# Motor_Drivers.net
KiCad netlist of a schematic drawn in Altium Designer
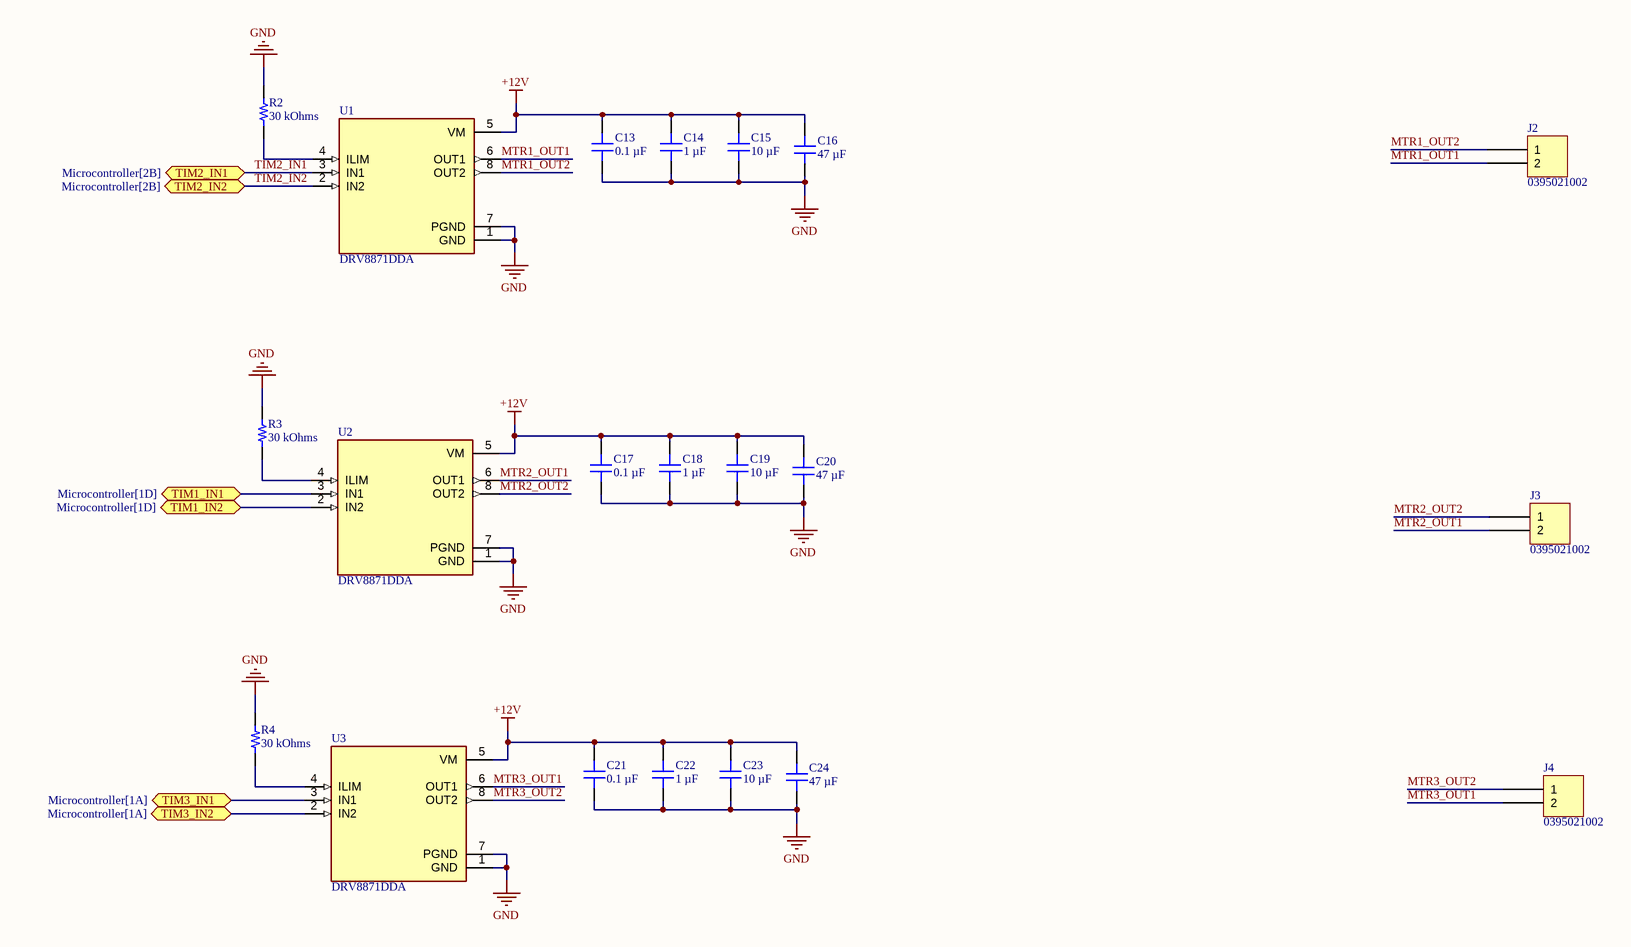
[diagram p0: Motor_Drivers.SchDoc]

(export (version "E")
  (design (tool "Eeschema 10.0.6"))
  (components
    (comp (ref "C13")
      (value "0.1 µF")
      (footprint "CAP 0603_1608")
      (description "CAP CER 0.1UF 25V X7R 0603")
      (fields
        (field (name "PART NUMBER") "C0603X104M3RAC7867")
        (field (name "CAPACITANCE") "0.1 µF")
        (field (name "MANUFACTURER") "KEMET")
      )
      (libsource (lib "Celestial Altium Library - altium_library") (part "Capacitor"))
    )
    (comp (ref "C14")
      (value "1 µF")
      (footprint "MURATA GCM188 0603_1608")
      (description "CAP CER 1UF 16V X7R 0603")
      (fields
        (field (name "PART NUMBER") "GCM188R71C105KA64J")
        (field (name "CAPACITANCE") "1 µF")
        (field (name "MANUFACTURER") "Murata Electronics")
      )
      (libsource (lib "Celestial Altium Library - altium_library") (part "Capacitor"))
    )
    (comp (ref "C15")
      (value "10 µF")
      (footprint "CAP 0603_1608")
      (description "CAP CER 10UF 16V X5R 0603")
      (fields
        (field (name "PART NUMBER") "CC0603MRX5R7BB106")
        (field (name "CAPACITANCE") "10 µF")
        (field (name "MANUFACTURER") "Yageo")
      )
      (libsource (lib "Celestial Altium Library - altium_library") (part "Capacitor"))
    )
    (comp (ref "C16")
      (value "47 µF")
      (footprint "MURATA CAP GRM31C 1206_3216")
      (description "CAP CER 47UF 25V X5R 1206")
      (fields
        (field (name "PART NUMBER") "GRM31CR61E476ME44L")
        (field (name "CAPACITANCE") "47 µF")
        (field (name "MANUFACTURER") "Murata Electronics")
      )
      (libsource (lib "Celestial Altium Library - altium_library") (part "Capacitor"))
    )
    (comp (ref "C17")
      (value "0.1 µF")
      (footprint "CAP 0603_1608")
      (description "CAP CER 0.1UF 25V X7R 0603")
      (fields
        (field (name "PART NUMBER") "C0603X104M3RAC7867")
        (field (name "CAPACITANCE") "0.1 µF")
        (field (name "MANUFACTURER") "KEMET")
      )
      (libsource (lib "Celestial Altium Library - altium_library") (part "Capacitor"))
    )
    (comp (ref "C18")
      (value "1 µF")
      (footprint "MURATA GCM188 0603_1608")
      (description "CAP CER 1UF 16V X7R 0603")
      (fields
        (field (name "PART NUMBER") "GCM188R71C105KA64J")
        (field (name "CAPACITANCE") "1 µF")
        (field (name "MANUFACTURER") "Murata Electronics")
      )
      (libsource (lib "Celestial Altium Library - altium_library") (part "Capacitor"))
    )
    (comp (ref "C19")
      (value "10 µF")
      (footprint "CAP 0603_1608")
      (description "CAP CER 10UF 16V X5R 0603")
      (fields
        (field (name "PART NUMBER") "CC0603MRX5R7BB106")
        (field (name "CAPACITANCE") "10 µF")
        (field (name "MANUFACTURER") "Yageo")
      )
      (libsource (lib "Celestial Altium Library - altium_library") (part "Capacitor"))
    )
    (comp (ref "C20")
      (value "47 µF")
      (footprint "MURATA CAP GRM31C 1206_3216")
      (description "CAP CER 47UF 25V X5R 1206")
      (fields
        (field (name "PART NUMBER") "GRM31CR61E476ME44L")
        (field (name "CAPACITANCE") "47 µF")
        (field (name "MANUFACTURER") "Murata Electronics")
      )
      (libsource (lib "Celestial Altium Library - altium_library") (part "Capacitor"))
    )
    (comp (ref "C21")
      (value "0.1 µF")
      (footprint "CAP 0603_1608")
      (description "CAP CER 0.1UF 25V X7R 0603")
      (fields
        (field (name "PART NUMBER") "C0603X104M3RAC7867")
        (field (name "CAPACITANCE") "0.1 µF")
        (field (name "MANUFACTURER") "KEMET")
      )
      (libsource (lib "Celestial Altium Library - altium_library") (part "Capacitor"))
    )
    (comp (ref "C22")
      (value "1 µF")
      (footprint "MURATA GCM188 0603_1608")
      (description "CAP CER 1UF 16V X7R 0603")
      (fields
        (field (name "PART NUMBER") "GCM188R71C105KA64J")
        (field (name "CAPACITANCE") "1 µF")
        (field (name "MANUFACTURER") "Murata Electronics")
      )
      (libsource (lib "Celestial Altium Library - altium_library") (part "Capacitor"))
    )
    (comp (ref "C23")
      (value "10 µF")
      (footprint "CAP 0603_1608")
      (description "CAP CER 10UF 16V X5R 0603")
      (fields
        (field (name "PART NUMBER") "CC0603MRX5R7BB106")
        (field (name "CAPACITANCE") "10 µF")
        (field (name "MANUFACTURER") "Yageo")
      )
      (libsource (lib "Celestial Altium Library - altium_library") (part "Capacitor"))
    )
    (comp (ref "C24")
      (value "47 µF")
      (footprint "MURATA CAP GRM31C 1206_3216")
      (description "CAP CER 47UF 25V X5R 1206")
      (fields
        (field (name "PART NUMBER") "GRM31CR61E476ME44L")
        (field (name "CAPACITANCE") "47 µF")
        (field (name "MANUFACTURER") "Murata Electronics")
      )
      (libsource (lib "Celestial Altium Library - altium_library") (part "Capacitor"))
    )
    (comp (ref "J2")
      (value "0395021002")
      (footprint "MOLEX 395021002")
      (description "TERM BLOCK HDR 2POS 90DEG 3.5MM")
      (fields (field (name "MANUFACTURER") "Molex"))
      (libsource (lib "Celestial Altium Library - altium_library") (part "2 Pin"))
    )
    (comp (ref "J3")
      (value "0395021002")
      (footprint "MOLEX 395021002")
      (description "TERM BLOCK HDR 2POS 90DEG 3.5MM")
      (fields (field (name "MANUFACTURER") "Molex"))
      (libsource (lib "Celestial Altium Library - altium_library") (part "2 Pin"))
    )
    (comp (ref "J4")
      (value "0395021002")
      (footprint "MOLEX 395021002")
      (description "TERM BLOCK HDR 2POS 90DEG 3.5MM")
      (fields (field (name "MANUFACTURER") "Molex"))
      (libsource (lib "Celestial Altium Library - altium_library") (part "2 Pin"))
    )
    (comp (ref "R2")
      (value "30 kOhms")
      (footprint "YAGEO RES 0402_1005")
      (description "RES 30K OHM 1% 1/16W 0402")
      (fields (field (name "PART NUMBER") "RC0402FR-1330KL") (field (name "MANUFACTURER") "Yageo"))
      (libsource (lib "Celestial Altium Library - altium_library") (part "Resistor"))
    )
    (comp (ref "R3")
      (value "30 kOhms")
      (footprint "YAGEO RES 0402_1005")
      (description "RES 30K OHM 1% 1/16W 0402")
      (fields (field (name "PART NUMBER") "RC0402FR-1330KL") (field (name "MANUFACTURER") "Yageo"))
      (libsource (lib "Celestial Altium Library - altium_library") (part "Resistor"))
    )
    (comp (ref "R4")
      (value "30 kOhms")
      (footprint "YAGEO RES 0402_1005")
      (description "RES 30K OHM 1% 1/16W 0402")
      (fields (field (name "PART NUMBER") "RC0402FR-1330KL") (field (name "MANUFACTURER") "Yageo"))
      (libsource (lib "Celestial Altium Library - altium_library") (part "Resistor"))
    )
    (comp (ref "U1")
      (value "DRV8871DDA")
      (footprint "DRV8871DDA")
      (description "Unipolar Motor Driver NMOS PWM 8-SO PowerPad")
      (fields (field (name "MANUFACTURER") "Texas Instrument"))
      (libsource (lib "PCB_Lib") (part "DRV8871DDA"))
    )
    (comp (ref "U2")
      (value "DRV8871DDA")
      (footprint "DRV8871DDA")
      (description "Unipolar Motor Driver NMOS PWM 8-SO PowerPad")
      (fields (field (name "MANUFACTURER") "Texas Instrument"))
      (libsource (lib "PCB_Lib") (part "DRV8871DDA"))
    )
    (comp (ref "U3")
      (value "DRV8871DDA")
      (footprint "DRV8871DDA")
      (description "Unipolar Motor Driver NMOS PWM 8-SO PowerPad")
      (fields (field (name "MANUFACTURER") "Texas Instrument"))
      (libsource (lib "PCB_Lib") (part "DRV8871DDA"))
    )
  )
  (nets
    (net (code "1") (name "+12V") (class "Default")
      (node (ref "C13") (pin "2") (pinfunction "2_2") (pintype "passive"))
      (node (ref "C14") (pin "2") (pinfunction "2_2") (pintype "passive"))
      (node (ref "C15") (pin "2") (pinfunction "2_2") (pintype "passive"))
      (node (ref "C16") (pin "2") (pinfunction "2_2") (pintype "passive"))
      (node (ref "C17") (pin "2") (pinfunction "2_2") (pintype "passive"))
      (node (ref "C18") (pin "2") (pinfunction "2_2") (pintype "passive"))
      (node (ref "C19") (pin "2") (pinfunction "2_2") (pintype "passive"))
      (node (ref "C20") (pin "2") (pinfunction "2_2") (pintype "passive"))
      (node (ref "C21") (pin "2") (pinfunction "2_2") (pintype "passive"))
      (node (ref "C22") (pin "2") (pinfunction "2_2") (pintype "passive"))
      (node (ref "C23") (pin "2") (pinfunction "2_2") (pintype "passive"))
      (node (ref "C24") (pin "2") (pinfunction "2_2") (pintype "passive"))
      (node (ref "U1") (pin "5") (pinfunction "VM_5") (pintype "power_in"))
      (node (ref "U2") (pin "5") (pinfunction "VM_5") (pintype "power_in"))
      (node (ref "U3") (pin "5") (pinfunction "VM_5") (pintype "power_in"))
    )
    (net (code "2") (name "/MTR1_OUT1") (class "Default")
      (node (ref "J2") (pin "2") (pinfunction "2_2") (pintype "passive"))
      (node (ref "U1") (pin "6") (pinfunction "OUT1_6") (pintype "output"))
    )
    (net (code "3") (name "/MTR1_OUT2") (class "Default")
      (node (ref "J2") (pin "1") (pinfunction "1_1") (pintype "passive"))
      (node (ref "U1") (pin "8") (pinfunction "OUT2_8") (pintype "output"))
    )
    (net (code "4") (name "/MTR2_OUT1") (class "Default")
      (node (ref "J3") (pin "2") (pinfunction "2_2") (pintype "passive"))
      (node (ref "U2") (pin "6") (pinfunction "OUT1_6") (pintype "output"))
    )
    (net (code "5") (name "/MTR2_OUT2") (class "Default")
      (node (ref "J3") (pin "1") (pinfunction "1_1") (pintype "passive"))
      (node (ref "U2") (pin "8") (pinfunction "OUT2_8") (pintype "output"))
    )
    (net (code "6") (name "/MTR3_OUT1") (class "Default")
      (node (ref "J4") (pin "2") (pinfunction "2_2") (pintype "passive"))
      (node (ref "U3") (pin "6") (pinfunction "OUT1_6") (pintype "output"))
    )
    (net (code "7") (name "/MTR3_OUT2") (class "Default")
      (node (ref "J4") (pin "1") (pinfunction "1_1") (pintype "passive"))
      (node (ref "U3") (pin "8") (pinfunction "OUT2_8") (pintype "output"))
    )
    (net (code "8") (name "/TIM1_IN1") (class "Default")
      (node (ref "U2") (pin "3") (pinfunction "IN1_3") (pintype "input"))
    )
    (net (code "9") (name "/TIM1_IN2") (class "Default")
      (node (ref "U2") (pin "2") (pinfunction "IN2_2") (pintype "input"))
    )
    (net (code "10") (name "/TIM2_IN1") (class "Default")
      (node (ref "U1") (pin "3") (pinfunction "IN1_3") (pintype "input"))
    )
    (net (code "11") (name "/TIM2_IN2") (class "Default")
      (node (ref "U1") (pin "2") (pinfunction "IN2_2") (pintype "input"))
    )
    (net (code "12") (name "/TIM3_IN1") (class "Default")
      (node (ref "U3") (pin "3") (pinfunction "IN1_3") (pintype "input"))
    )
    (net (code "13") (name "/TIM3_IN2") (class "Default")
      (node (ref "U3") (pin "2") (pinfunction "IN2_2") (pintype "input"))
    )
    (net (code "14") (name "GND") (class "Default")
      (node (ref "C13") (pin "1") (pinfunction "1_1") (pintype "passive"))
      (node (ref "C14") (pin "1") (pinfunction "1_1") (pintype "passive"))
      (node (ref "C15") (pin "1") (pinfunction "1_1") (pintype "passive"))
      (node (ref "C16") (pin "1") (pinfunction "1_1") (pintype "passive"))
      (node (ref "C17") (pin "1") (pinfunction "1_1") (pintype "passive"))
      (node (ref "C18") (pin "1") (pinfunction "1_1") (pintype "passive"))
      (node (ref "C19") (pin "1") (pinfunction "1_1") (pintype "passive"))
      (node (ref "C20") (pin "1") (pinfunction "1_1") (pintype "passive"))
      (node (ref "C21") (pin "1") (pinfunction "1_1") (pintype "passive"))
      (node (ref "C22") (pin "1") (pinfunction "1_1") (pintype "passive"))
      (node (ref "C23") (pin "1") (pinfunction "1_1") (pintype "passive"))
      (node (ref "C24") (pin "1") (pinfunction "1_1") (pintype "passive"))
      (node (ref "R2") (pin "2") (pinfunction "2_2") (pintype "passive"))
      (node (ref "R3") (pin "2") (pinfunction "2_2") (pintype "passive"))
      (node (ref "R4") (pin "2") (pinfunction "2_2") (pintype "passive"))
      (node (ref "U1") (pin "1") (pinfunction "GND_1") (pintype "power_in"))
      (node (ref "U1") (pin "7") (pinfunction "PGND_7") (pintype "power_in"))
      (node (ref "U2") (pin "1") (pinfunction "GND_1") (pintype "power_in"))
      (node (ref "U2") (pin "7") (pinfunction "PGND_7") (pintype "power_in"))
      (node (ref "U3") (pin "1") (pinfunction "GND_1") (pintype "power_in"))
      (node (ref "U3") (pin "7") (pinfunction "PGND_7") (pintype "power_in"))
    )
    (net (code "15") (name "Net-(U1-ILIM)") (class "Default")
      (node (ref "R2") (pin "1") (pinfunction "1_1") (pintype "passive"))
      (node (ref "U1") (pin "4") (pinfunction "ILIM_4") (pintype "input"))
    )
    (net (code "16") (name "Net-(U2-ILIM)") (class "Default")
      (node (ref "R3") (pin "1") (pinfunction "1_1") (pintype "passive"))
      (node (ref "U2") (pin "4") (pinfunction "ILIM_4") (pintype "input"))
    )
    (net (code "17") (name "Net-(U3-ILIM)") (class "Default")
      (node (ref "R4") (pin "1") (pinfunction "1_1") (pintype "passive"))
      (node (ref "U3") (pin "4") (pinfunction "ILIM_4") (pintype "input"))
    )
  )
)
